# hubi2c-n32.net
KiCad netlist of a schematic drawn in EAGLE
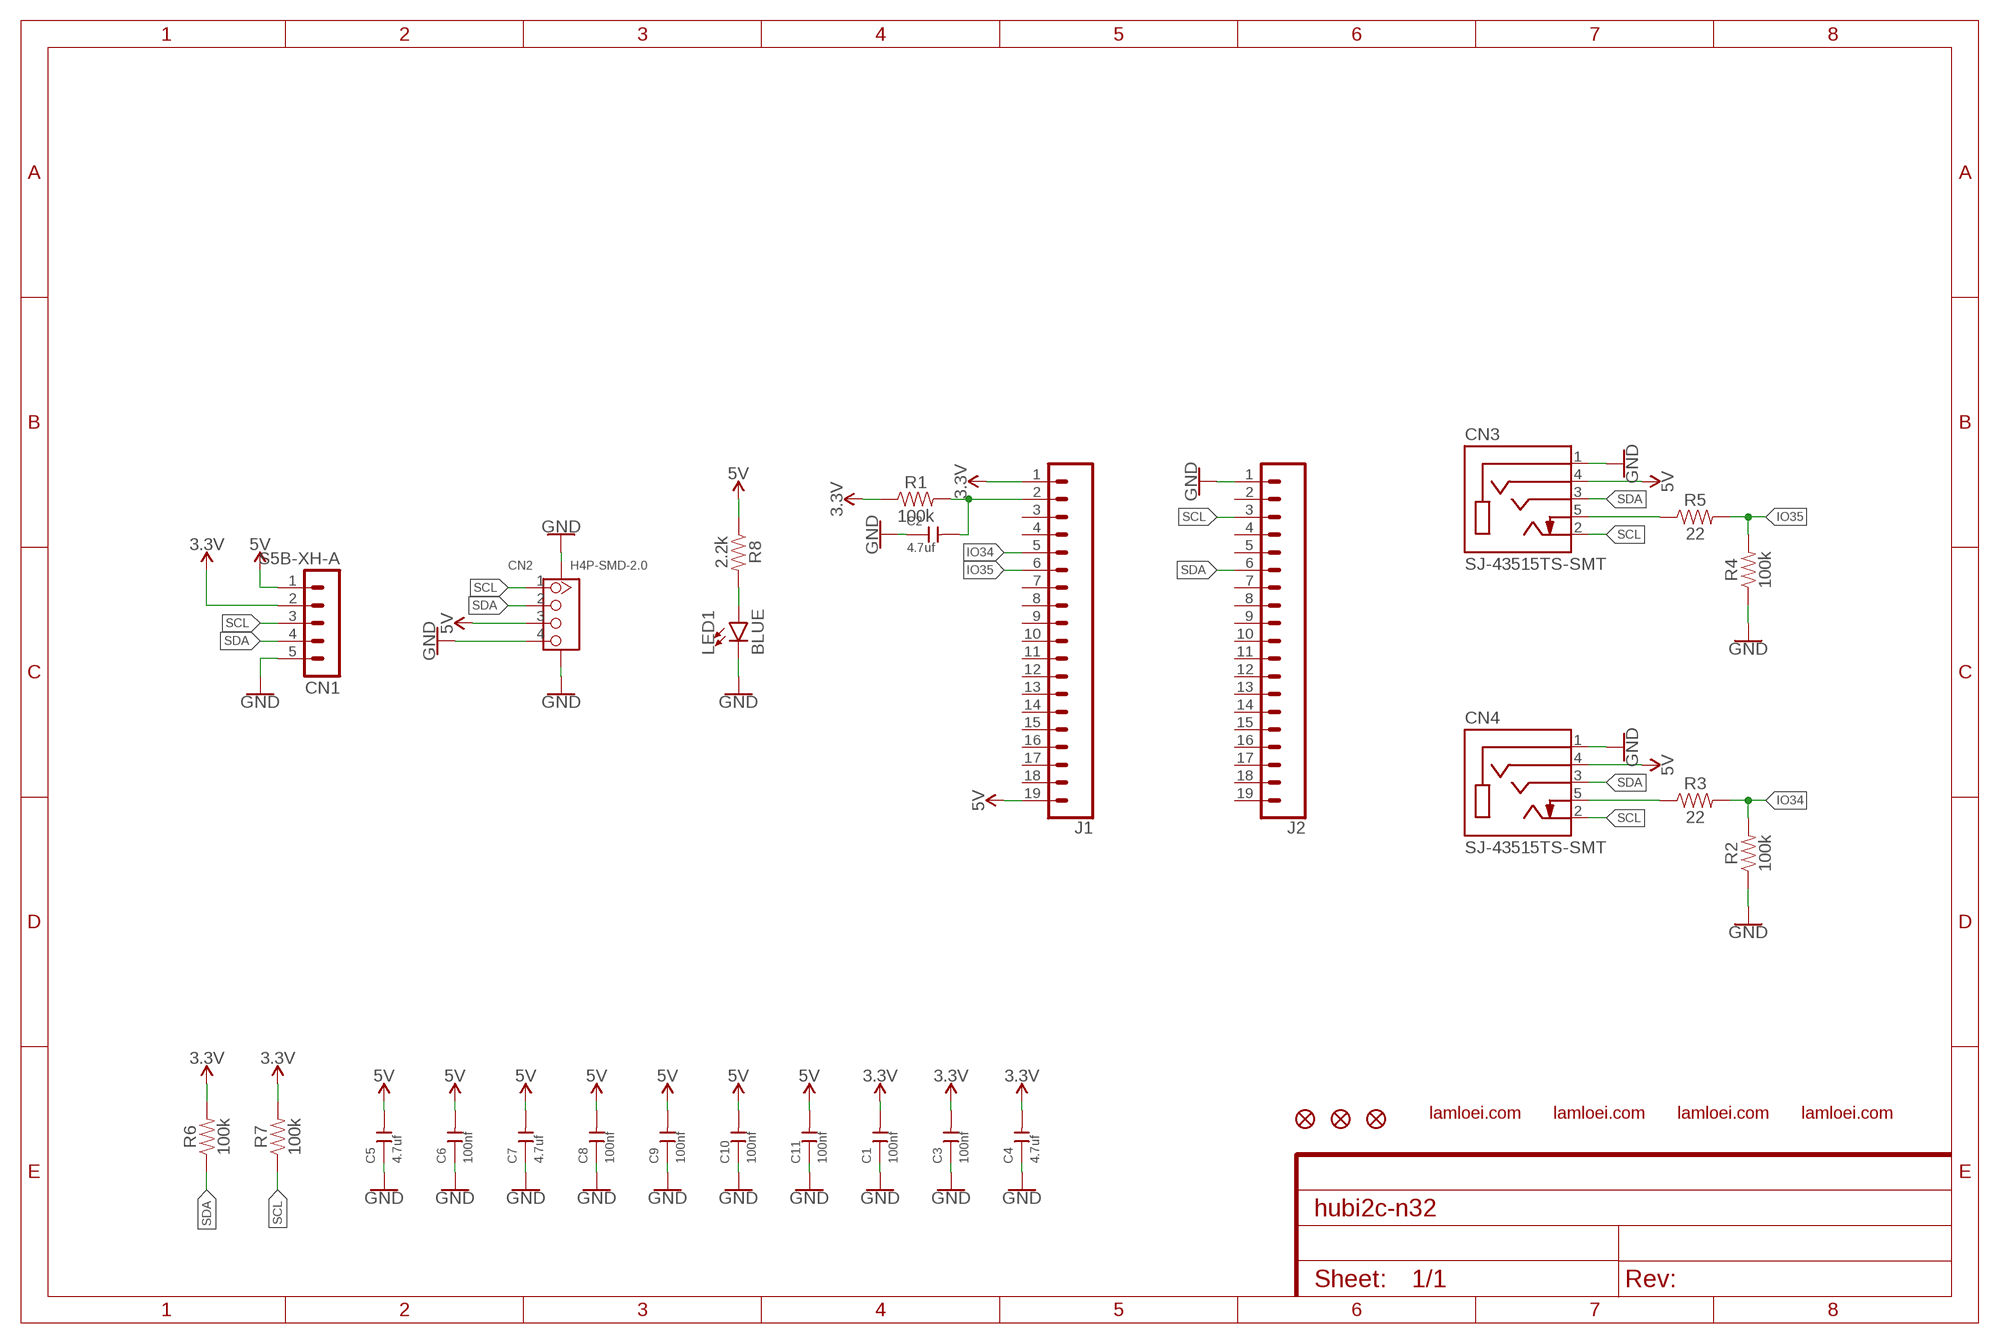
[diagram p0: schematic, sheet 1]

(export (version "E")
  (design (tool "Eeschema 10.0.6"))
  (components
    (comp (ref "C1")
      (value "100nf")
      (footprint "eagle-import:C0402")
      (fields (field (name "MPN") "CC0402KRX7R8BB104"))
      (libsource (lib "eagle-import") (part "CERAMIC-100NF-25V-10%-X7R(0402)"))
    )
    (comp (ref "C2")
      (value "4.7uf")
      (footprint "eagle-import:C0603")
      (fields (field (name "MPN") "CC0603KRX5R6BB475"))
      (libsource (lib "eagle-import") (part "CERAMIC-4.7UF-10V-10%-X5R(0603)"))
    )
    (comp (ref "C3")
      (value "100nf")
      (footprint "eagle-import:C0402")
      (fields (field (name "MPN") "CC0402KRX7R8BB104"))
      (libsource (lib "eagle-import") (part "CERAMIC-100NF-25V-10%-X7R(0402)"))
    )
    (comp (ref "C4")
      (value "4.7uf")
      (footprint "eagle-import:C0603")
      (fields (field (name "MPN") "CC0603KRX5R6BB475"))
      (libsource (lib "eagle-import") (part "CERAMIC-4.7UF-10V-10%-X5R(0603)"))
    )
    (comp (ref "C5")
      (value "4.7uf")
      (footprint "eagle-import:C0603")
      (fields (field (name "MPN") "CC0603KRX5R6BB475"))
      (libsource (lib "eagle-import") (part "CERAMIC-4.7UF-10V-10%-X5R(0603)"))
    )
    (comp (ref "C6")
      (value "100nf")
      (footprint "eagle-import:C0402")
      (fields (field (name "MPN") "CC0402KRX7R8BB104"))
      (libsource (lib "eagle-import") (part "CERAMIC-100NF-25V-10%-X7R(0402)"))
    )
    (comp (ref "C7")
      (value "4.7uf")
      (footprint "eagle-import:C0603")
      (fields (field (name "MPN") "CC0603KRX5R6BB475"))
      (libsource (lib "eagle-import") (part "CERAMIC-4.7UF-10V-10%-X5R(0603)"))
    )
    (comp (ref "C8")
      (value "100nf")
      (footprint "eagle-import:C0402")
      (fields (field (name "MPN") "CC0402KRX7R8BB104"))
      (libsource (lib "eagle-import") (part "CERAMIC-100NF-25V-10%-X7R(0402)"))
    )
    (comp (ref "C9")
      (value "100nf")
      (footprint "eagle-import:C0402")
      (fields (field (name "MPN") "CC0402KRX7R8BB104"))
      (libsource (lib "eagle-import") (part "CERAMIC-100NF-25V-10%-X7R(0402)"))
    )
    (comp (ref "C10")
      (value "100nf")
      (footprint "eagle-import:C0402")
      (fields (field (name "MPN") "CC0402KRX7R8BB104"))
      (libsource (lib "eagle-import") (part "CERAMIC-100NF-25V-10%-X7R(0402)"))
    )
    (comp (ref "C11")
      (value "100nf")
      (footprint "eagle-import:C0402")
      (fields (field (name "MPN") "CC0402KRX7R8BB104"))
      (libsource (lib "eagle-import") (part "CERAMIC-100NF-25V-10%-X7R(0402)"))
    )
    (comp (ref "CN1")
      (value "S5B-XH-A")
      (footprint "eagle-import:S5B-XH-A")
      (libsource (lib "eagle-import") (part "S5B-XH-A"))
    )
    (comp (ref "CN2")
      (value "H4P-SMD-2.0")
      (footprint "eagle-import:HW4-SMD-2.0")
      (libsource (lib "eagle-import") (part "GROVE-CONNECTOR-SMD(4+2P-2.0)"))
    )
    (comp (ref "CN3")
      (value "SJ-43515TS-SMT")
      (footprint "eagle-import:CUI_SJ-43515TS-SMT")
      (fields (field (name "MF") "CUI Devices") (field (name "MP") "SJ-43515TS-SMT-TR"))
      (libsource (lib "eagle-import") (part "SJ-43515TS-SMT"))
    )
    (comp (ref "CN4")
      (value "SJ-43515TS-SMT")
      (footprint "eagle-import:CUI_SJ-43515TS-SMT")
      (fields (field (name "MF") "CUI Devices") (field (name "MP") "SJ-43515TS-SMT-TR"))
      (libsource (lib "eagle-import") (part "SJ-43515TS-SMT"))
    )
    (comp (ref "J1")
      (value "CONN_19")
      (footprint "eagle-import:1X19")
      (libsource (lib "eagle-import") (part "CONN_19"))
    )
    (comp (ref "J2")
      (value "CONN_19")
      (footprint "eagle-import:1X19")
      (libsource (lib "eagle-import") (part "SparkFun-Connectors-3_CONN_19"))
    )
    (comp (ref "LED1")
      (value "BLUE")
      (footprint "eagle-import:LED-0603")
      (libsource (lib "eagle-import") (part "LED-BLUE0603"))
    )
    (comp (ref "R1")
      (value "100k")
      (footprint "eagle-import:0603")
      (libsource (lib "eagle-import") (part "100KOHM-0603-1/10W-1%"))
    )
    (comp (ref "R2")
      (value "100k")
      (footprint "eagle-import:0603")
      (libsource (lib "eagle-import") (part "100KOHM-0603-1/10W-1%"))
    )
    (comp (ref "R3")
      (value "22")
      (footprint "eagle-import:0603")
      (libsource (lib "eagle-import") (part "0OHM-0603-1/10W"))
    )
    (comp (ref "R4")
      (value "100k")
      (footprint "eagle-import:0603")
      (libsource (lib "eagle-import") (part "100KOHM-0603-1/10W-1%"))
    )
    (comp (ref "R5")
      (value "22")
      (footprint "eagle-import:0603")
      (libsource (lib "eagle-import") (part "0OHM-0603-1/10W"))
    )
    (comp (ref "R6")
      (value "100k")
      (footprint "eagle-import:0603")
      (libsource (lib "eagle-import") (part "100KOHM-0603-1/10W-1%"))
    )
    (comp (ref "R7")
      (value "100k")
      (footprint "eagle-import:0603")
      (libsource (lib "eagle-import") (part "100KOHM-0603-1/10W-1%"))
    )
    (comp (ref "R8")
      (value "2.2k")
      (footprint "eagle-import:0603")
      (libsource (lib "eagle-import") (part "2.2KOHM-0603-1/10W-1%"))
    )
    (comp (ref "ZFD1")
      (value "FIDUCIAL1X2")
      (footprint "eagle-import:FIDUCIAL-1X2")
      (libsource (lib "eagle-import") (part "FIDUCIAL1X2"))
    )
    (comp (ref "ZFD2")
      (value "FIDUCIAL1X2")
      (footprint "eagle-import:FIDUCIAL-1X2")
      (libsource (lib "eagle-import") (part "FIDUCIAL1X2"))
    )
    (comp (ref "ZFD3")
      (value "FIDUCIAL1X2")
      (footprint "eagle-import:FIDUCIAL-1X2")
      (libsource (lib "eagle-import") (part "FIDUCIAL1X2"))
    )
    (comp (ref "ZL1")
      (value "LAMLEOI_LOGO_3")
      (footprint "eagle-import:LAMLEOI_LOGO_3")
      (libsource (lib "eagle-import") (part "LAMLEOI_LOGO_3"))
    )
    (comp (ref "ZL2")
      (value "LAMLEOI_LOGO_3")
      (footprint "eagle-import:LAMLEOI_LOGO_3")
      (libsource (lib "eagle-import") (part "LAMLEOI_LOGO_3"))
    )
    (comp (ref "ZL3")
      (value "LAMLEOI_LOGO_3")
      (footprint "eagle-import:LAMLEOI_LOGO_3")
      (libsource (lib "eagle-import") (part "LAMLEOI_LOGO_3"))
    )
    (comp (ref "ZL4")
      (value "LAMLOEI_BIGLOGO")
      (footprint "eagle-import:LAMLOEI_BIGLOGO")
      (libsource (lib "eagle-import") (part "LAMLOEI_BIGLOGO"))
    )
  )
  (nets
    (net (code "1") (name "3.3V") (class "Default")
      (node (ref "C1") (pin "2") (pinfunction "2_2") (pintype "passive"))
      (node (ref "C3") (pin "2") (pinfunction "2_2") (pintype "passive"))
      (node (ref "C4") (pin "2") (pinfunction "2_2") (pintype "passive"))
      (node (ref "CN1") (pin "2") (pinfunction "2_2") (pintype "passive"))
      (node (ref "J1") (pin "1") (pinfunction "1_1") (pintype "passive"))
      (node (ref "R1") (pin "1") (pinfunction "1_1") (pintype "passive"))
      (node (ref "R6") (pin "2") (pinfunction "2_2") (pintype "passive"))
      (node (ref "R7") (pin "2") (pinfunction "2_2") (pintype "passive"))
    )
    (net (code "2") (name "5V") (class "Default")
      (node (ref "C10") (pin "2") (pinfunction "2_2") (pintype "passive"))
      (node (ref "C11") (pin "2") (pinfunction "2_2") (pintype "passive"))
      (node (ref "C5") (pin "2") (pinfunction "2_2") (pintype "passive"))
      (node (ref "C6") (pin "2") (pinfunction "2_2") (pintype "passive"))
      (node (ref "C7") (pin "2") (pinfunction "2_2") (pintype "passive"))
      (node (ref "C8") (pin "2") (pinfunction "2_2") (pintype "passive"))
      (node (ref "C9") (pin "2") (pinfunction "2_2") (pintype "passive"))
      (node (ref "CN1") (pin "1") (pinfunction "1_1") (pintype "passive"))
      (node (ref "CN2") (pin "3") (pinfunction "3_3") (pintype "bidirectional"))
      (node (ref "CN3") (pin "4") (pinfunction "RING2_4") (pintype "passive"))
      (node (ref "CN4") (pin "4") (pinfunction "RING2_4") (pintype "passive"))
      (node (ref "J1") (pin "19") (pinfunction "19_19") (pintype "passive"))
      (node (ref "R8") (pin "1") (pinfunction "1_1") (pintype "passive"))
    )
    (net (code "3") (name "GND") (class "Default")
      (node (ref "C1") (pin "1") (pinfunction "1_1") (pintype "passive"))
      (node (ref "C10") (pin "1") (pinfunction "1_1") (pintype "passive"))
      (node (ref "C11") (pin "1") (pinfunction "1_1") (pintype "passive"))
      (node (ref "C2") (pin "1") (pinfunction "1_1") (pintype "passive"))
      (node (ref "C3") (pin "1") (pinfunction "1_1") (pintype "passive"))
      (node (ref "C4") (pin "1") (pinfunction "1_1") (pintype "passive"))
      (node (ref "C5") (pin "1") (pinfunction "1_1") (pintype "passive"))
      (node (ref "C6") (pin "1") (pinfunction "1_1") (pintype "passive"))
      (node (ref "C7") (pin "1") (pinfunction "1_1") (pintype "passive"))
      (node (ref "C8") (pin "1") (pinfunction "1_1") (pintype "passive"))
      (node (ref "C9") (pin "1") (pinfunction "1_1") (pintype "passive"))
      (node (ref "CN1") (pin "5") (pinfunction "5_5") (pintype "passive"))
      (node (ref "CN2") (pin "4") (pinfunction "4_4") (pintype "bidirectional"))
      (node (ref "CN2") (pin "SS1") (pinfunction "SS1_SS1") (pintype "bidirectional"))
      (node (ref "CN2") (pin "SS2") (pinfunction "SS2_SS2") (pintype "bidirectional"))
      (node (ref "CN3") (pin "1") (pinfunction "SLEEVE_1") (pintype "passive"))
      (node (ref "CN4") (pin "1") (pinfunction "SLEEVE_1") (pintype "passive"))
      (node (ref "J2") (pin "1") (pinfunction "1_1") (pintype "passive"))
      (node (ref "LED1") (pin "C") (pinfunction "C_C") (pintype "passive"))
      (node (ref "R2") (pin "1") (pinfunction "1_1") (pintype "passive"))
      (node (ref "R4") (pin "1") (pinfunction "1_1") (pintype "passive"))
    )
    (net (code "4") (name "IO34") (class "Default")
      (node (ref "J1") (pin "5") (pinfunction "5_5") (pintype "passive"))
      (node (ref "R2") (pin "2") (pinfunction "2_2") (pintype "passive"))
      (node (ref "R3") (pin "2") (pinfunction "2_2") (pintype "passive"))
    )
    (net (code "5") (name "IO35") (class "Default")
      (node (ref "J1") (pin "6") (pinfunction "6_6") (pintype "passive"))
      (node (ref "R4") (pin "2") (pinfunction "2_2") (pintype "passive"))
      (node (ref "R5") (pin "2") (pinfunction "2_2") (pintype "passive"))
    )
    (net (code "6") (name "Net-(C2-Pad2)") (class "Default")
      (node (ref "C2") (pin "2") (pinfunction "2_2") (pintype "passive"))
      (node (ref "J1") (pin "2") (pinfunction "2_2") (pintype "passive"))
      (node (ref "R1") (pin "2") (pinfunction "2_2") (pintype "passive"))
    )
    (net (code "7") (name "Net-(CN3-TIP_SWITCH)") (class "Default")
      (node (ref "CN3") (pin "5") (pinfunction "TIP_SWITCH_5") (pintype "passive"))
      (node (ref "R5") (pin "1") (pinfunction "1_1") (pintype "passive"))
    )
    (net (code "8") (name "Net-(CN4-TIP_SWITCH)") (class "Default")
      (node (ref "CN4") (pin "5") (pinfunction "TIP_SWITCH_5") (pintype "passive"))
      (node (ref "R3") (pin "1") (pinfunction "1_1") (pintype "passive"))
    )
    (net (code "9") (name "Net-(LED1-PadA)") (class "Default")
      (node (ref "LED1") (pin "A") (pinfunction "A_A") (pintype "passive"))
      (node (ref "R8") (pin "2") (pinfunction "2_2") (pintype "passive"))
    )
    (net (code "10") (name "SCL") (class "Default")
      (node (ref "CN1") (pin "3") (pinfunction "3_3") (pintype "passive"))
      (node (ref "CN2") (pin "1") (pinfunction "1_1") (pintype "bidirectional"))
      (node (ref "CN3") (pin "2") (pinfunction "TIP_2") (pintype "passive"))
      (node (ref "CN4") (pin "2") (pinfunction "TIP_2") (pintype "passive"))
      (node (ref "J2") (pin "3") (pinfunction "3_3") (pintype "passive"))
      (node (ref "R7") (pin "1") (pinfunction "1_1") (pintype "passive"))
    )
    (net (code "11") (name "SDA") (class "Default")
      (node (ref "CN1") (pin "4") (pinfunction "4_4") (pintype "passive"))
      (node (ref "CN2") (pin "2") (pinfunction "2_2") (pintype "bidirectional"))
      (node (ref "CN3") (pin "3") (pinfunction "RING1_3") (pintype "passive"))
      (node (ref "CN4") (pin "3") (pinfunction "RING1_3") (pintype "passive"))
      (node (ref "J2") (pin "6") (pinfunction "6_6") (pintype "passive"))
      (node (ref "R6") (pin "1") (pinfunction "1_1") (pintype "passive"))
    )
    (net (code "12") (name "unconnected-(J1-Pad3)") (class "Default")
      (node (ref "J1") (pin "3") (pinfunction "3_3") (pintype "passive"))
    )
    (net (code "13") (name "unconnected-(J1-Pad4)") (class "Default")
      (node (ref "J1") (pin "4") (pinfunction "4_4") (pintype "passive"))
    )
    (net (code "14") (name "unconnected-(J1-Pad7)") (class "Default")
      (node (ref "J1") (pin "7") (pinfunction "7_7") (pintype "passive"))
    )
    (net (code "15") (name "unconnected-(J1-Pad8)") (class "Default")
      (node (ref "J1") (pin "8") (pinfunction "8_8") (pintype "passive"))
    )
    (net (code "16") (name "unconnected-(J1-Pad9)") (class "Default")
      (node (ref "J1") (pin "9") (pinfunction "9_9") (pintype "passive"))
    )
    (net (code "17") (name "unconnected-(J1-Pad10)") (class "Default")
      (node (ref "J1") (pin "10") (pinfunction "10_10") (pintype "passive"))
    )
    (net (code "18") (name "unconnected-(J1-Pad11)") (class "Default")
      (node (ref "J1") (pin "11") (pinfunction "11_11") (pintype "passive"))
    )
    (net (code "19") (name "unconnected-(J1-Pad12)") (class "Default")
      (node (ref "J1") (pin "12") (pinfunction "12_12") (pintype "passive"))
    )
    (net (code "20") (name "unconnected-(J1-Pad13)") (class "Default")
      (node (ref "J1") (pin "13") (pinfunction "13_13") (pintype "passive"))
    )
    (net (code "21") (name "unconnected-(J1-Pad14)") (class "Default")
      (node (ref "J1") (pin "14") (pinfunction "14_14") (pintype "passive"))
    )
    (net (code "22") (name "unconnected-(J1-Pad15)") (class "Default")
      (node (ref "J1") (pin "15") (pinfunction "15_15") (pintype "passive"))
    )
    (net (code "23") (name "unconnected-(J1-Pad16)") (class "Default")
      (node (ref "J1") (pin "16") (pinfunction "16_16") (pintype "passive"))
    )
    (net (code "24") (name "unconnected-(J1-Pad17)") (class "Default")
      (node (ref "J1") (pin "17") (pinfunction "17_17") (pintype "passive"))
    )
    (net (code "25") (name "unconnected-(J1-Pad18)") (class "Default")
      (node (ref "J1") (pin "18") (pinfunction "18_18") (pintype "passive"))
    )
    (net (code "26") (name "unconnected-(J2-Pad2)") (class "Default")
      (node (ref "J2") (pin "2") (pinfunction "2_2") (pintype "passive"))
    )
    (net (code "27") (name "unconnected-(J2-Pad4)") (class "Default")
      (node (ref "J2") (pin "4") (pinfunction "4_4") (pintype "passive"))
    )
    (net (code "28") (name "unconnected-(J2-Pad5)") (class "Default")
      (node (ref "J2") (pin "5") (pinfunction "5_5") (pintype "passive"))
    )
    (net (code "29") (name "unconnected-(J2-Pad7)") (class "Default")
      (node (ref "J2") (pin "7") (pinfunction "7_7") (pintype "passive"))
    )
    (net (code "30") (name "unconnected-(J2-Pad8)") (class "Default")
      (node (ref "J2") (pin "8") (pinfunction "8_8") (pintype "passive"))
    )
    (net (code "31") (name "unconnected-(J2-Pad9)") (class "Default")
      (node (ref "J2") (pin "9") (pinfunction "9_9") (pintype "passive"))
    )
    (net (code "32") (name "unconnected-(J2-Pad10)") (class "Default")
      (node (ref "J2") (pin "10") (pinfunction "10_10") (pintype "passive"))
    )
    (net (code "33") (name "unconnected-(J2-Pad11)") (class "Default")
      (node (ref "J2") (pin "11") (pinfunction "11_11") (pintype "passive"))
    )
    (net (code "34") (name "unconnected-(J2-Pad12)") (class "Default")
      (node (ref "J2") (pin "12") (pinfunction "12_12") (pintype "passive"))
    )
    (net (code "35") (name "unconnected-(J2-Pad13)") (class "Default")
      (node (ref "J2") (pin "13") (pinfunction "13_13") (pintype "passive"))
    )
    (net (code "36") (name "unconnected-(J2-Pad14)") (class "Default")
      (node (ref "J2") (pin "14") (pinfunction "14_14") (pintype "passive"))
    )
    (net (code "37") (name "unconnected-(J2-Pad15)") (class "Default")
      (node (ref "J2") (pin "15") (pinfunction "15_15") (pintype "passive"))
    )
    (net (code "38") (name "unconnected-(J2-Pad16)") (class "Default")
      (node (ref "J2") (pin "16") (pinfunction "16_16") (pintype "passive"))
    )
    (net (code "39") (name "unconnected-(J2-Pad17)") (class "Default")
      (node (ref "J2") (pin "17") (pinfunction "17_17") (pintype "passive"))
    )
    (net (code "40") (name "unconnected-(J2-Pad18)") (class "Default")
      (node (ref "J2") (pin "18") (pinfunction "18_18") (pintype "passive"))
    )
    (net (code "41") (name "unconnected-(J2-Pad19)") (class "Default")
      (node (ref "J2") (pin "19") (pinfunction "19_19") (pintype "passive"))
    )
  )
)
